# PQ60_EPS_FV2.net
KiCad netlist of a schematic drawn in EAGLE
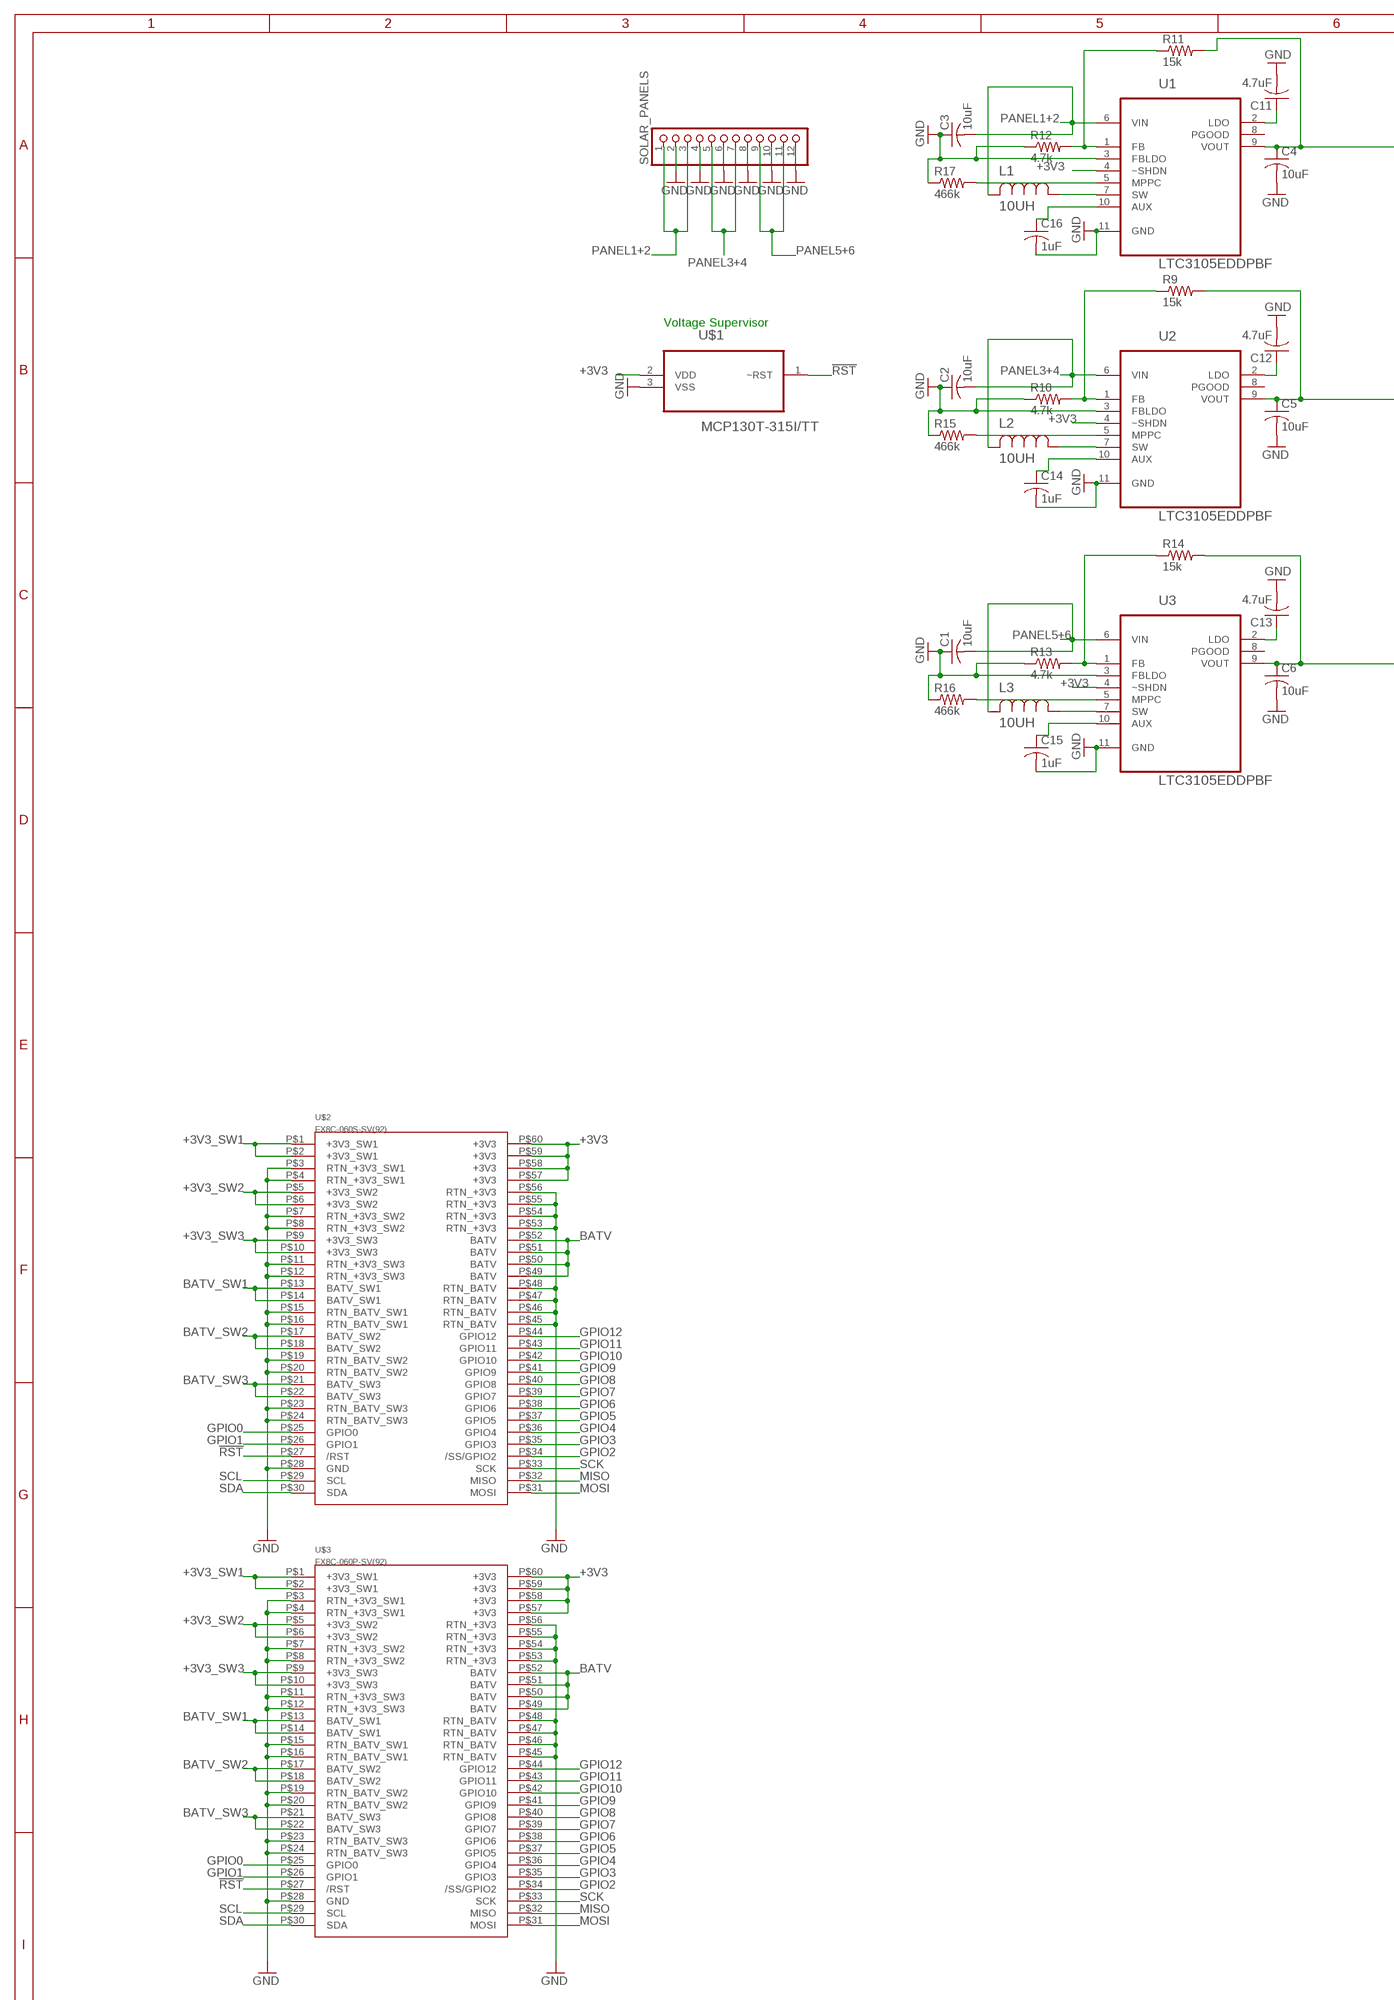
[diagram p0: schematic, sheet 1, part 1 of 2]
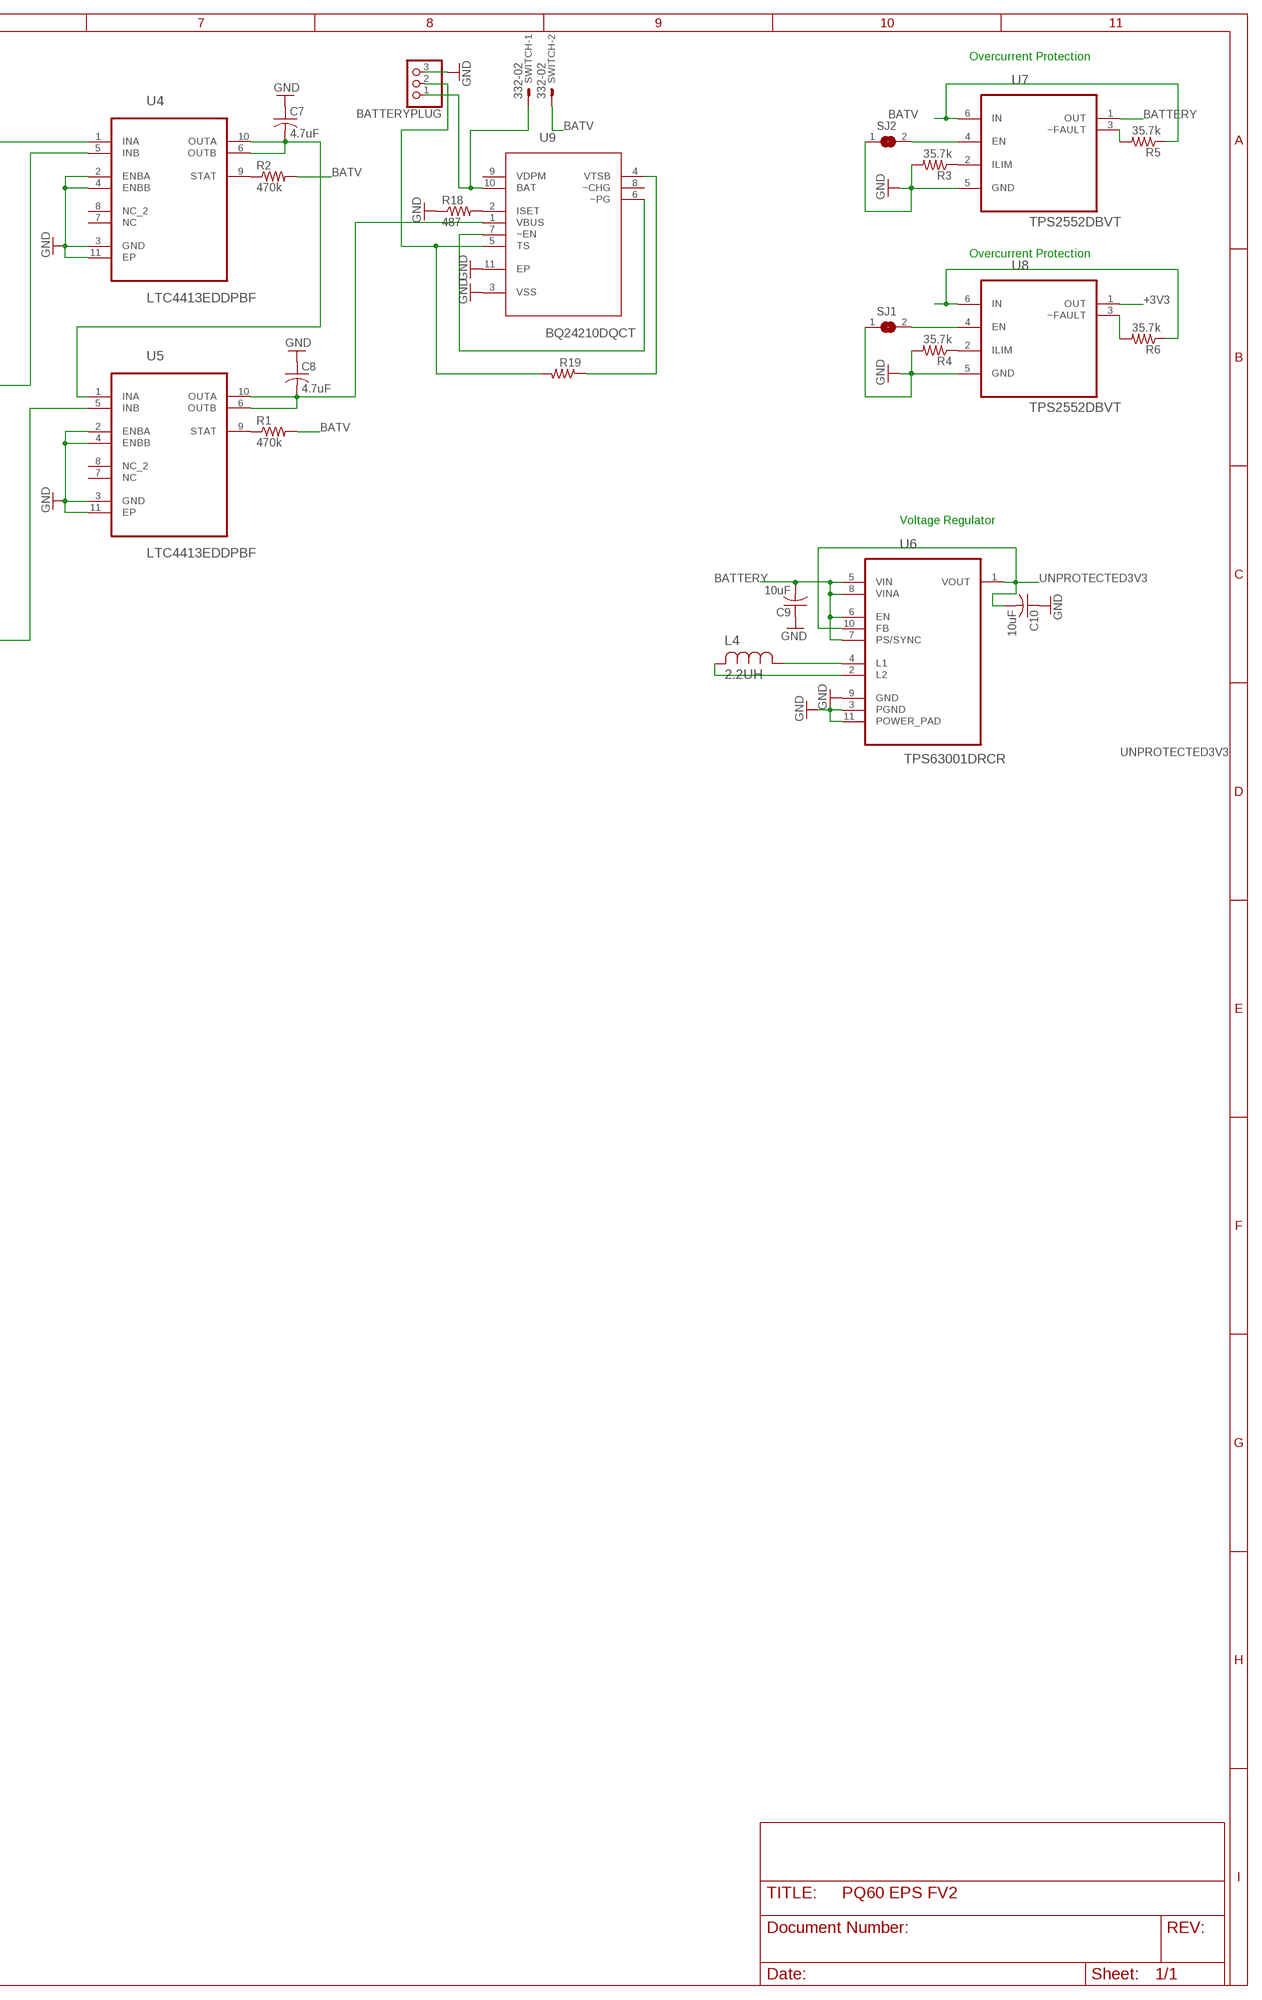
[diagram p1: schematic, sheet 1, part 2 of 2]

(export (version "E")
  (design (tool "Eeschema 10.0.6"))
  (components
    (comp (ref "BATTERYPLUG")
      (value "PINHD-1X3")
      (footprint "eagle-import:1X03")
      (libsource (lib "eagle-import") (part "PINHD-1X3"))
    )
    (comp (ref "C1")
      (value "10uF")
      (footprint "eagle-import:C0805")
      (libsource (lib "eagle-import") (part "C-USC0805"))
    )
    (comp (ref "C2")
      (value "10uF")
      (footprint "eagle-import:C0805")
      (libsource (lib "eagle-import") (part "C-USC0805"))
    )
    (comp (ref "C3")
      (value "10uF")
      (footprint "eagle-import:C0805")
      (libsource (lib "eagle-import") (part "C-USC0805"))
    )
    (comp (ref "C4")
      (value "10uF")
      (footprint "eagle-import:C0805")
      (libsource (lib "eagle-import") (part "C-USC0805"))
    )
    (comp (ref "C5")
      (value "10uF")
      (footprint "eagle-import:C0805")
      (libsource (lib "eagle-import") (part "C-USC0805"))
    )
    (comp (ref "C6")
      (value "10uF")
      (footprint "eagle-import:C0805")
      (libsource (lib "eagle-import") (part "C-USC0805"))
    )
    (comp (ref "C7")
      (value "4.7uF")
      (footprint "eagle-import:C0805")
      (libsource (lib "eagle-import") (part "C-USC0805"))
    )
    (comp (ref "C8")
      (value "4.7uF")
      (footprint "eagle-import:C0805")
      (libsource (lib "eagle-import") (part "C-USC0805"))
    )
    (comp (ref "C9")
      (value "10uF")
      (footprint "eagle-import:C0805")
      (libsource (lib "eagle-import") (part "C-USC0805"))
    )
    (comp (ref "C10")
      (value "10uF")
      (footprint "eagle-import:C0805")
      (libsource (lib "eagle-import") (part "C-USC0805"))
    )
    (comp (ref "C11")
      (value "4.7uF")
      (footprint "eagle-import:C0805")
      (libsource (lib "eagle-import") (part "C-USC0805"))
    )
    (comp (ref "C12")
      (value "4.7uF")
      (footprint "eagle-import:C0805")
      (libsource (lib "eagle-import") (part "C-USC0805"))
    )
    (comp (ref "C13")
      (value "4.7uF")
      (footprint "eagle-import:C0805")
      (libsource (lib "eagle-import") (part "C-USC0805"))
    )
    (comp (ref "C14")
      (value "1uF")
      (footprint "eagle-import:C0805")
      (libsource (lib "eagle-import") (part "C-USC0805"))
    )
    (comp (ref "C15")
      (value "1uF")
      (footprint "eagle-import:C0805")
      (libsource (lib "eagle-import") (part "C-USC0805"))
    )
    (comp (ref "C16")
      (value "1uF")
      (footprint "eagle-import:C0805")
      (libsource (lib "eagle-import") (part "C-USC0805"))
    )
    (comp (ref "L1")
      (value "10UH")
      (footprint "eagle-import:IND_ELL6XH")
      (fields (field (name "MPN") "ELL6SH100M"))
      (libsource (lib "eagle-import") (part "ELL-6XH6SH100M"))
    )
    (comp (ref "L2")
      (value "10UH")
      (footprint "eagle-import:IND_ELL6XH")
      (fields (field (name "MPN") "ELL6SH100M"))
      (libsource (lib "eagle-import") (part "ELL-6XH6SH100M"))
    )
    (comp (ref "L3")
      (value "10UH")
      (footprint "eagle-import:IND_ELL6XH")
      (fields (field (name "MPN") "ELL6SH100M"))
      (libsource (lib "eagle-import") (part "ELL-6XH6SH100M"))
    )
    (comp (ref "L4")
      (value "2.2UH")
      (footprint "eagle-import:IND_ELL3FU")
      (fields (field (name "MPN") "ELL3FU2R2N") (field (name "TOLERANCE") "±30 %"))
      (libsource (lib "eagle-import") (part "ELL-3FU3FU2R2N"))
    )
    (comp (ref "R1")
      (value "470k")
      (footprint "eagle-import:R0805")
      (libsource (lib "eagle-import") (part "R-US_R0805"))
    )
    (comp (ref "R2")
      (value "470k")
      (footprint "eagle-import:R0805")
      (libsource (lib "eagle-import") (part "R-US_R0805"))
    )
    (comp (ref "R3")
      (value "35.7k")
      (footprint "eagle-import:R0805")
      (libsource (lib "eagle-import") (part "R-US_R0805"))
    )
    (comp (ref "R4")
      (value "35.7k")
      (footprint "eagle-import:R0805")
      (libsource (lib "eagle-import") (part "R-US_R0805"))
    )
    (comp (ref "R5")
      (value "35.7k")
      (footprint "eagle-import:R0805")
      (libsource (lib "eagle-import") (part "R-US_R0805"))
    )
    (comp (ref "R6")
      (value "35.7k")
      (footprint "eagle-import:R0805")
      (libsource (lib "eagle-import") (part "R-US_R0805"))
    )
    (comp (ref "R9")
      (value "15k")
      (footprint "eagle-import:R0805")
      (libsource (lib "eagle-import") (part "R-US_R0805"))
    )
    (comp (ref "R10")
      (value "4.7k")
      (footprint "eagle-import:R0805")
      (libsource (lib "eagle-import") (part "R-US_R0805"))
    )
    (comp (ref "R11")
      (value "15k")
      (footprint "eagle-import:R0805")
      (libsource (lib "eagle-import") (part "R-US_R0805"))
    )
    (comp (ref "R12")
      (value "4.7k")
      (footprint "eagle-import:R0805")
      (libsource (lib "eagle-import") (part "R-US_R0805"))
    )
    (comp (ref "R13")
      (value "4.7k")
      (footprint "eagle-import:R0805")
      (libsource (lib "eagle-import") (part "R-US_R0805"))
    )
    (comp (ref "R14")
      (value "15k")
      (footprint "eagle-import:R0805")
      (libsource (lib "eagle-import") (part "R-US_R0805"))
    )
    (comp (ref "R15")
      (value "466k")
      (footprint "eagle-import:R0805")
      (libsource (lib "eagle-import") (part "R-US_R0805"))
    )
    (comp (ref "R16")
      (value "466k")
      (footprint "eagle-import:R0805")
      (libsource (lib "eagle-import") (part "R-US_R0805"))
    )
    (comp (ref "R17")
      (value "466k")
      (footprint "eagle-import:R0805")
      (libsource (lib "eagle-import") (part "R-US_R0805"))
    )
    (comp (ref "R18")
      (value "487")
      (footprint "eagle-import:R0805")
      (libsource (lib "eagle-import") (part "R-US_R0805"))
    )
    (comp (ref "R19")
      (value "R-US_R0805")
      (footprint "eagle-import:R0805")
      (libsource (lib "eagle-import") (part "R-US_R0805"))
    )
    (comp (ref "SJ1") (value "SJ") (footprint "eagle-import:SJ") (libsource (lib "eagle-import") (part "SJ")))
    (comp (ref "SJ2") (value "SJ") (footprint "eagle-import:SJ") (libsource (lib "eagle-import") (part "SJ")))
    (comp (ref "SOLAR_PANELS")
      (value "PINHD-1X12-CB")
      (footprint "eagle-import:1X12-CB")
      (libsource (lib "eagle-import") (part "PINHD-1X12-CB"))
    )
    (comp (ref "SWITCH")
      (value "332-02")
      (footprint "eagle-import:332-02")
      (libsource (lib "eagle-import") (part "332-02"))
    )
    (comp (ref "U$1")
      (value "MCP130T-315I/TT")
      (footprint "eagle-import:SOT95P237X112-3N")
      (libsource (lib "eagle-import") (part "MCP130T-315I/TT"))
    )
    (comp (ref "U$2")
      (value "FX8C-060S-SV(92)")
      (footprint "eagle-import:FX8C-060S-SV(92)")
      (libsource (lib "eagle-import") (part "FX8C-060S-SV(92)"))
    )
    (comp (ref "U$3")
      (value "FX8C-060P-SV(92)")
      (footprint "eagle-import:FX8C-060P-SV(92)")
      (libsource (lib "eagle-import") (part "FX8C-060P-SV(92)"))
    )
    (comp (ref "U1")
      (value "LTC3105EDDPBF")
      (footprint "eagle-import:DFN300X300X80-11N")
      (fields (field (name "MPN") "LTC3105EDD#PBF"))
      (libsource (lib "eagle-import") (part "LTC3105EDDPBF"))
    )
    (comp (ref "U2")
      (value "LTC3105EDDPBF")
      (footprint "eagle-import:DFN300X300X80-11N")
      (fields (field (name "MPN") "LTC3105EDD#PBF"))
      (libsource (lib "eagle-import") (part "LTC3105EDDPBF"))
    )
    (comp (ref "U3")
      (value "LTC3105EDDPBF")
      (footprint "eagle-import:DFN300X300X80-11N")
      (fields (field (name "MPN") "LTC3105EDD#PBF"))
      (libsource (lib "eagle-import") (part "LTC3105EDDPBF"))
    )
    (comp (ref "U4")
      (value "LTC4413EDDPBF")
      (footprint "eagle-import:DFN300X300X80-11N")
      (fields (field (name "MPN") "LTC4413EDD#PBF"))
      (libsource (lib "eagle-import") (part "LTC4413EDDPBF"))
    )
    (comp (ref "U5")
      (value "LTC4413EDDPBF")
      (footprint "eagle-import:DFN300X300X80-11N")
      (fields (field (name "MPN") "LTC4413EDD#PBF"))
      (libsource (lib "eagle-import") (part "LTC4413EDDPBF"))
    )
    (comp (ref "U6")
      (value "TPS63001DRCR")
      (footprint "eagle-import:SON50P300X300X100-11N")
      (libsource (lib "eagle-import") (part "TPS63001DRCR"))
    )
    (comp (ref "U7")
      (value "TPS2552DBVT")
      (footprint "eagle-import:SOT95P280X145-6N")
      (libsource (lib "eagle-import") (part "TPS2552DBVT"))
    )
    (comp (ref "U8")
      (value "TPS2552DBVT")
      (footprint "eagle-import:SOT95P280X145-6N")
      (libsource (lib "eagle-import") (part "TPS2552DBVT"))
    )
    (comp (ref "U9")
      (value "BQ24210DQCT")
      (footprint "eagle-import:SON50P200X300X80-11N")
      (libsource (lib "eagle-import") (part "BQ24210DQCT"))
    )
  )
  (nets
    (net (code "1") (name "/+3V3") (class "Default")
      (node (ref "U$1") (pin "2") (pinfunction "VDD_2") (pintype "power_in"))
      (node (ref "U$2") (pin "P$57") (pinfunction "+3V3_P$57") (pintype "power_in"))
      (node (ref "U$2") (pin "P$58") (pinfunction "+3V3_P$58") (pintype "power_in"))
      (node (ref "U$2") (pin "P$59") (pinfunction "+3V3_P$59") (pintype "power_in"))
      (node (ref "U$2") (pin "P$60") (pinfunction "+3V3_P$60") (pintype "power_in"))
      (node (ref "U$3") (pin "P$57") (pinfunction "+3V3_P$57") (pintype "power_in"))
      (node (ref "U$3") (pin "P$58") (pinfunction "+3V3_P$58") (pintype "power_in"))
      (node (ref "U$3") (pin "P$59") (pinfunction "+3V3_P$59") (pintype "power_in"))
      (node (ref "U$3") (pin "P$60") (pinfunction "+3V3_P$60") (pintype "power_in"))
      (node (ref "U1") (pin "4") (pinfunction "~{SHDN}_4") (pintype "input"))
      (node (ref "U2") (pin "4") (pinfunction "~{SHDN}_4") (pintype "input"))
      (node (ref "U3") (pin "4") (pinfunction "~{SHDN}_4") (pintype "input"))
      (node (ref "U8") (pin "1") (pinfunction "OUT_1") (pintype "output"))
    )
    (net (code "2") (name "/+3V3_SW1") (class "Default")
      (node (ref "U$2") (pin "P$1") (pinfunction "+3V3_SW1_P$1") (pintype "power_in"))
      (node (ref "U$2") (pin "P$2") (pinfunction "+3V3_SW1_P$2") (pintype "power_in"))
      (node (ref "U$3") (pin "P$1") (pinfunction "+3V3_SW1_P$1") (pintype "power_in"))
      (node (ref "U$3") (pin "P$2") (pinfunction "+3V3_SW1_P$2") (pintype "power_in"))
    )
    (net (code "3") (name "/+3V3_SW2") (class "Default")
      (node (ref "U$2") (pin "P$5") (pinfunction "+3V3_SW2_P$5") (pintype "power_in"))
      (node (ref "U$2") (pin "P$6") (pinfunction "+3V3_SW2_P$6") (pintype "power_in"))
      (node (ref "U$3") (pin "P$5") (pinfunction "+3V3_SW2_P$5") (pintype "power_in"))
      (node (ref "U$3") (pin "P$6") (pinfunction "+3V3_SW2_P$6") (pintype "power_in"))
    )
    (net (code "4") (name "/+3V3_SW3") (class "Default")
      (node (ref "U$2") (pin "P$10") (pinfunction "+3V3_SW3_P$10") (pintype "power_in"))
      (node (ref "U$2") (pin "P$9") (pinfunction "+3V3_SW3_P$9") (pintype "power_in"))
      (node (ref "U$3") (pin "P$10") (pinfunction "+3V3_SW3_P$10") (pintype "power_in"))
      (node (ref "U$3") (pin "P$9") (pinfunction "+3V3_SW3_P$9") (pintype "power_in"))
    )
    (net (code "5") (name "/BATTERY") (class "Default")
      (node (ref "C9") (pin "2") (pinfunction "2_2") (pintype "passive"))
      (node (ref "U6") (pin "5") (pinfunction "VIN_5") (pintype "power_in"))
      (node (ref "U6") (pin "6") (pinfunction "EN_6") (pintype "input"))
      (node (ref "U6") (pin "7") (pinfunction "PS/SYNC_7") (pintype "input"))
      (node (ref "U6") (pin "8") (pinfunction "VINA_8") (pintype "power_in"))
      (node (ref "U7") (pin "1") (pinfunction "OUT_1") (pintype "output"))
    )
    (net (code "6") (name "/BATV") (class "Default")
      (node (ref "R1") (pin "2") (pinfunction "2_2") (pintype "passive"))
      (node (ref "R2") (pin "2") (pinfunction "2_2") (pintype "passive"))
      (node (ref "R5") (pin "1") (pinfunction "1_1") (pintype "passive"))
      (node (ref "SWITCH") (pin "2") (pinfunction "S_2") (pintype "passive"))
      (node (ref "U$2") (pin "P$49") (pinfunction "BATV_P$49") (pintype "power_in"))
      (node (ref "U$2") (pin "P$50") (pinfunction "BATV_P$50") (pintype "power_in"))
      (node (ref "U$2") (pin "P$51") (pinfunction "BATV_P$51") (pintype "power_in"))
      (node (ref "U$2") (pin "P$52") (pinfunction "BATV_P$52") (pintype "power_in"))
      (node (ref "U$3") (pin "P$49") (pinfunction "BATV_P$49") (pintype "power_in"))
      (node (ref "U$3") (pin "P$50") (pinfunction "BATV_P$50") (pintype "power_in"))
      (node (ref "U$3") (pin "P$51") (pinfunction "BATV_P$51") (pintype "power_in"))
      (node (ref "U$3") (pin "P$52") (pinfunction "BATV_P$52") (pintype "power_in"))
      (node (ref "U7") (pin "6") (pinfunction "IN_6") (pintype "power_in"))
    )
    (net (code "7") (name "/BATV_SW1") (class "Default")
      (node (ref "U$2") (pin "P$13") (pinfunction "BATV_SW1_P$13") (pintype "power_in"))
      (node (ref "U$2") (pin "P$14") (pinfunction "BATV_SW1_P$14") (pintype "power_in"))
      (node (ref "U$3") (pin "P$13") (pinfunction "BATV_SW1_P$13") (pintype "power_in"))
      (node (ref "U$3") (pin "P$14") (pinfunction "BATV_SW1_P$14") (pintype "power_in"))
    )
    (net (code "8") (name "/BATV_SW2") (class "Default")
      (node (ref "U$2") (pin "P$17") (pinfunction "BATV_SW2_P$17") (pintype "power_in"))
      (node (ref "U$2") (pin "P$18") (pinfunction "BATV_SW2_P$18") (pintype "power_in"))
      (node (ref "U$3") (pin "P$17") (pinfunction "BATV_SW2_P$17") (pintype "power_in"))
      (node (ref "U$3") (pin "P$18") (pinfunction "BATV_SW2_P$18") (pintype "power_in"))
    )
    (net (code "9") (name "/BATV_SW3") (class "Default")
      (node (ref "U$2") (pin "P$21") (pinfunction "BATV_SW3_P$21") (pintype "power_in"))
      (node (ref "U$2") (pin "P$22") (pinfunction "BATV_SW3_P$22") (pintype "power_in"))
      (node (ref "U$3") (pin "P$21") (pinfunction "BATV_SW3_P$21") (pintype "power_in"))
      (node (ref "U$3") (pin "P$22") (pinfunction "BATV_SW3_P$22") (pintype "power_in"))
    )
    (net (code "10") (name "/GPIO0") (class "Default")
      (node (ref "U$2") (pin "P$25") (pinfunction "GPIO0_P$25") (pintype "bidirectional"))
      (node (ref "U$3") (pin "P$25") (pinfunction "GPIO0_P$25") (pintype "bidirectional"))
    )
    (net (code "11") (name "/GPIO1") (class "Default")
      (node (ref "U$2") (pin "P$26") (pinfunction "GPIO1_P$26") (pintype "bidirectional"))
      (node (ref "U$3") (pin "P$26") (pinfunction "GPIO1_P$26") (pintype "bidirectional"))
    )
    (net (code "12") (name "/GPIO2") (class "Default")
      (node (ref "U$2") (pin "P$34") (pinfunction "/SS/GPIO2_P$34") (pintype "bidirectional"))
      (node (ref "U$3") (pin "P$34") (pinfunction "/SS/GPIO2_P$34") (pintype "bidirectional"))
    )
    (net (code "13") (name "/GPIO3") (class "Default")
      (node (ref "U$2") (pin "P$35") (pinfunction "GPIO3_P$35") (pintype "bidirectional"))
      (node (ref "U$3") (pin "P$35") (pinfunction "GPIO3_P$35") (pintype "bidirectional"))
    )
    (net (code "14") (name "/GPIO4") (class "Default")
      (node (ref "U$2") (pin "P$36") (pinfunction "GPIO4_P$36") (pintype "bidirectional"))
      (node (ref "U$3") (pin "P$36") (pinfunction "GPIO4_P$36") (pintype "bidirectional"))
    )
    (net (code "15") (name "/GPIO5") (class "Default")
      (node (ref "U$2") (pin "P$37") (pinfunction "GPIO5_P$37") (pintype "bidirectional"))
      (node (ref "U$3") (pin "P$37") (pinfunction "GPIO5_P$37") (pintype "bidirectional"))
    )
    (net (code "16") (name "/GPIO6") (class "Default")
      (node (ref "U$2") (pin "P$38") (pinfunction "GPIO6_P$38") (pintype "bidirectional"))
      (node (ref "U$3") (pin "P$38") (pinfunction "GPIO6_P$38") (pintype "bidirectional"))
    )
    (net (code "17") (name "/GPIO7") (class "Default")
      (node (ref "U$2") (pin "P$39") (pinfunction "GPIO7_P$39") (pintype "bidirectional"))
      (node (ref "U$3") (pin "P$39") (pinfunction "GPIO7_P$39") (pintype "bidirectional"))
    )
    (net (code "18") (name "/GPIO8") (class "Default")
      (node (ref "U$2") (pin "P$40") (pinfunction "GPIO8_P$40") (pintype "bidirectional"))
      (node (ref "U$3") (pin "P$40") (pinfunction "GPIO8_P$40") (pintype "bidirectional"))
    )
    (net (code "19") (name "/GPIO9") (class "Default")
      (node (ref "U$2") (pin "P$41") (pinfunction "GPIO9_P$41") (pintype "bidirectional"))
      (node (ref "U$3") (pin "P$41") (pinfunction "GPIO9_P$41") (pintype "bidirectional"))
    )
    (net (code "20") (name "/GPIO10") (class "Default")
      (node (ref "U$2") (pin "P$42") (pinfunction "GPIO10_P$42") (pintype "bidirectional"))
      (node (ref "U$3") (pin "P$42") (pinfunction "GPIO10_P$42") (pintype "bidirectional"))
    )
    (net (code "21") (name "/GPIO11") (class "Default")
      (node (ref "U$2") (pin "P$43") (pinfunction "GPIO11_P$43") (pintype "bidirectional"))
      (node (ref "U$3") (pin "P$43") (pinfunction "GPIO11_P$43") (pintype "bidirectional"))
    )
    (net (code "22") (name "/GPIO12") (class "Default")
      (node (ref "U$2") (pin "P$44") (pinfunction "GPIO12_P$44") (pintype "bidirectional"))
      (node (ref "U$3") (pin "P$44") (pinfunction "GPIO12_P$44") (pintype "bidirectional"))
    )
    (net (code "23") (name "/MISO") (class "Default")
      (node (ref "U$2") (pin "P$32") (pinfunction "MISO_P$32") (pintype "bidirectional"))
      (node (ref "U$3") (pin "P$32") (pinfunction "MISO_P$32") (pintype "bidirectional"))
    )
    (net (code "24") (name "/MOSI") (class "Default")
      (node (ref "U$2") (pin "P$31") (pinfunction "MOSI_P$31") (pintype "bidirectional"))
      (node (ref "U$3") (pin "P$31") (pinfunction "MOSI_P$31") (pintype "bidirectional"))
    )
    (net (code "25") (name "/PANEL1+2") (class "Default")
      (node (ref "C3") (pin "2") (pinfunction "2_2") (pintype "passive"))
      (node (ref "L1") (pin "2") (pinfunction "2_2") (pintype "passive"))
      (node (ref "SOLAR_PANELS") (pin "1") (pinfunction "1_1") (pintype "passive"))
      (node (ref "SOLAR_PANELS") (pin "3") (pinfunction "3_3") (pintype "passive"))
      (node (ref "U1") (pin "6") (pinfunction "VIN_6") (pintype "power_in"))
    )
    (net (code "26") (name "/PANEL3+4") (class "Default")
      (node (ref "C2") (pin "2") (pinfunction "2_2") (pintype "passive"))
      (node (ref "L2") (pin "2") (pinfunction "2_2") (pintype "passive"))
      (node (ref "SOLAR_PANELS") (pin "5") (pinfunction "5_5") (pintype "passive"))
      (node (ref "SOLAR_PANELS") (pin "7") (pinfunction "7_7") (pintype "passive"))
      (node (ref "U2") (pin "6") (pinfunction "VIN_6") (pintype "power_in"))
    )
    (net (code "27") (name "/PANEL5+6") (class "Default")
      (node (ref "C1") (pin "2") (pinfunction "2_2") (pintype "passive"))
      (node (ref "L3") (pin "2") (pinfunction "2_2") (pintype "passive"))
      (node (ref "SOLAR_PANELS") (pin "11") (pinfunction "11_11") (pintype "passive"))
      (node (ref "SOLAR_PANELS") (pin "9") (pinfunction "9_9") (pintype "passive"))
      (node (ref "U3") (pin "6") (pinfunction "VIN_6") (pintype "power_in"))
    )
    (net (code "28") (name "/SCK") (class "Default")
      (node (ref "U$2") (pin "P$33") (pinfunction "SCK_P$33") (pintype "bidirectional"))
      (node (ref "U$3") (pin "P$33") (pinfunction "SCK_P$33") (pintype "bidirectional"))
    )
    (net (code "29") (name "/SCL") (class "Default")
      (node (ref "U$2") (pin "P$29") (pinfunction "SCL_P$29") (pintype "bidirectional"))
      (node (ref "U$3") (pin "P$29") (pinfunction "SCL_P$29") (pintype "bidirectional"))
    )
    (net (code "30") (name "/SDA") (class "Default")
      (node (ref "U$2") (pin "P$30") (pinfunction "SDA_P$30") (pintype "bidirectional"))
      (node (ref "U$3") (pin "P$30") (pinfunction "SDA_P$30") (pintype "bidirectional"))
    )
    (net (code "31") (name "/UNPROTECTED3V3") (class "Default")
      (node (ref "C10") (pin "2") (pinfunction "2_2") (pintype "passive"))
      (node (ref "R6") (pin "1") (pinfunction "1_1") (pintype "passive"))
      (node (ref "U6") (pin "1") (pinfunction "VOUT_1") (pintype "output"))
      (node (ref "U6") (pin "10") (pinfunction "FB_10") (pintype "input"))
      (node (ref "U8") (pin "6") (pinfunction "IN_6") (pintype "power_in"))
    )
    (net (code "32") (name "/~{RST}") (class "Default")
      (node (ref "U$1") (pin "1") (pinfunction "~{RST}_1") (pintype "output"))
      (node (ref "U$2") (pin "P$27") (pinfunction "/RST_P$27") (pintype "bidirectional"))
      (node (ref "U$3") (pin "P$27") (pinfunction "/RST_P$27") (pintype "bidirectional"))
    )
    (net (code "33") (name "GND") (class "Default")
      (node (ref "BATTERYPLUG") (pin "3") (pinfunction "3_3") (pintype "passive"))
      (node (ref "C1") (pin "1") (pinfunction "1_1") (pintype "passive"))
      (node (ref "C10") (pin "1") (pinfunction "1_1") (pintype "passive"))
      (node (ref "C11") (pin "2") (pinfunction "2_2") (pintype "passive"))
      (node (ref "C12") (pin "2") (pinfunction "2_2") (pintype "passive"))
      (node (ref "C13") (pin "2") (pinfunction "2_2") (pintype "passive"))
      (node (ref "C14") (pin "2") (pinfunction "2_2") (pintype "passive"))
      (node (ref "C15") (pin "2") (pinfunction "2_2") (pintype "passive"))
      (node (ref "C16") (pin "2") (pinfunction "2_2") (pintype "passive"))
      (node (ref "C2") (pin "1") (pinfunction "1_1") (pintype "passive"))
      (node (ref "C3") (pin "1") (pinfunction "1_1") (pintype "passive"))
      (node (ref "C4") (pin "2") (pinfunction "2_2") (pintype "passive"))
      (node (ref "C5") (pin "2") (pinfunction "2_2") (pintype "passive"))
      (node (ref "C6") (pin "2") (pinfunction "2_2") (pintype "passive"))
      (node (ref "C7") (pin "1") (pinfunction "1_1") (pintype "passive"))
      (node (ref "C8") (pin "1") (pinfunction "1_1") (pintype "passive"))
      (node (ref "C9") (pin "1") (pinfunction "1_1") (pintype "passive"))
      (node (ref "R10") (pin "1") (pinfunction "1_1") (pintype "passive"))
      (node (ref "R12") (pin "1") (pinfunction "1_1") (pintype "passive"))
      (node (ref "R13") (pin "1") (pinfunction "1_1") (pintype "passive"))
      (node (ref "R15") (pin "1") (pinfunction "1_1") (pintype "passive"))
      (node (ref "R16") (pin "1") (pinfunction "1_1") (pintype "passive"))
      (node (ref "R17") (pin "1") (pinfunction "1_1") (pintype "passive"))
      (node (ref "R18") (pin "1") (pinfunction "1_1") (pintype "passive"))
      (node (ref "R3") (pin "2") (pinfunction "2_2") (pintype "passive"))
      (node (ref "R4") (pin "2") (pinfunction "2_2") (pintype "passive"))
      (node (ref "SJ1") (pin "1") (pinfunction "1_1") (pintype "passive"))
      (node (ref "SJ2") (pin "1") (pinfunction "1_1") (pintype "passive"))
      (node (ref "SOLAR_PANELS") (pin "10") (pinfunction "10_10") (pintype "passive"))
      (node (ref "SOLAR_PANELS") (pin "12") (pinfunction "12_12") (pintype "passive"))
      (node (ref "SOLAR_PANELS") (pin "2") (pinfunction "2_2") (pintype "passive"))
      (node (ref "SOLAR_PANELS") (pin "4") (pinfunction "4_4") (pintype "passive"))
      (node (ref "SOLAR_PANELS") (pin "6") (pinfunction "6_6") (pintype "passive"))
      (node (ref "SOLAR_PANELS") (pin "8") (pinfunction "8_8") (pintype "passive"))
      (node (ref "U$1") (pin "3") (pinfunction "VSS_3") (pintype "power_in"))
      (node (ref "U$2") (pin "P$11") (pinfunction "RTN_+3V3_SW3_P$11") (pintype "power_in"))
      (node (ref "U$2") (pin "P$12") (pinfunction "RTN_+3V3_SW3_P$12") (pintype "power_in"))
      (node (ref "U$2") (pin "P$15") (pinfunction "RTN_BATV_SW1_P$15") (pintype "power_in"))
      (node (ref "U$2") (pin "P$16") (pinfunction "RTN_BATV_SW1_P$16") (pintype "power_in"))
      (node (ref "U$2") (pin "P$19") (pinfunction "RTN_BATV_SW2_P$19") (pintype "power_in"))
      (node (ref "U$2") (pin "P$20") (pinfunction "RTN_BATV_SW2_P$20") (pintype "power_in"))
      (node (ref "U$2") (pin "P$23") (pinfunction "RTN_BATV_SW3_P$23") (pintype "power_in"))
      (node (ref "U$2") (pin "P$24") (pinfunction "RTN_BATV_SW3_P$24") (pintype "power_in"))
      (node (ref "U$2") (pin "P$28") (pinfunction "GND_P$28") (pintype "bidirectional"))
      (node (ref "U$2") (pin "P$3") (pinfunction "RTN_+3V3_SW1_P$3") (pintype "power_in"))
      (node (ref "U$2") (pin "P$4") (pinfunction "RTN_+3V3_SW1_P$4") (pintype "power_in"))
      (node (ref "U$2") (pin "P$45") (pinfunction "RTN_BATV_P$45") (pintype "power_in"))
      (node (ref "U$2") (pin "P$46") (pinfunction "RTN_BATV_P$46") (pintype "power_in"))
      (node (ref "U$2") (pin "P$47") (pinfunction "RTN_BATV_P$47") (pintype "power_in"))
      (node (ref "U$2") (pin "P$48") (pinfunction "RTN_BATV_P$48") (pintype "power_in"))
      (node (ref "U$2") (pin "P$53") (pinfunction "RTN_+3V3_P$53") (pintype "power_in"))
      (node (ref "U$2") (pin "P$54") (pinfunction "RTN_+3V3_P$54") (pintype "power_in"))
      (node (ref "U$2") (pin "P$55") (pinfunction "RTN_+3V3_P$55") (pintype "power_in"))
      (node (ref "U$2") (pin "P$56") (pinfunction "RTN_+3V3_P$56") (pintype "power_in"))
      (node (ref "U$2") (pin "P$7") (pinfunction "RTN_+3V3_SW2_P$7") (pintype "power_in"))
      (node (ref "U$2") (pin "P$8") (pinfunction "RTN_+3V3_SW2_P$8") (pintype "power_in"))
      (node (ref "U$3") (pin "P$11") (pinfunction "RTN_+3V3_SW3_P$11") (pintype "power_in"))
      (node (ref "U$3") (pin "P$12") (pinfunction "RTN_+3V3_SW3_P$12") (pintype "power_in"))
      (node (ref "U$3") (pin "P$15") (pinfunction "RTN_BATV_SW1_P$15") (pintype "power_in"))
      (node (ref "U$3") (pin "P$16") (pinfunction "RTN_BATV_SW1_P$16") (pintype "power_in"))
      (node (ref "U$3") (pin "P$19") (pinfunction "RTN_BATV_SW2_P$19") (pintype "power_in"))
      (node (ref "U$3") (pin "P$20") (pinfunction "RTN_BATV_SW2_P$20") (pintype "power_in"))
      (node (ref "U$3") (pin "P$23") (pinfunction "RTN_BATV_SW3_P$23") (pintype "power_in"))
      (node (ref "U$3") (pin "P$24") (pinfunction "RTN_BATV_SW3_P$24") (pintype "power_in"))
      (node (ref "U$3") (pin "P$28") (pinfunction "GND_P$28") (pintype "bidirectional"))
      (node (ref "U$3") (pin "P$3") (pinfunction "RTN_+3V3_SW1_P$3") (pintype "power_in"))
      (node (ref "U$3") (pin "P$4") (pinfunction "RTN_+3V3_SW1_P$4") (pintype "power_in"))
      (node (ref "U$3") (pin "P$45") (pinfunction "RTN_BATV_P$45") (pintype "power_in"))
      (node (ref "U$3") (pin "P$46") (pinfunction "RTN_BATV_P$46") (pintype "power_in"))
      (node (ref "U$3") (pin "P$47") (pinfunction "RTN_BATV_P$47") (pintype "power_in"))
      (node (ref "U$3") (pin "P$48") (pinfunction "RTN_BATV_P$48") (pintype "power_in"))
      (node (ref "U$3") (pin "P$53") (pinfunction "RTN_+3V3_P$53") (pintype "power_in"))
      (node (ref "U$3") (pin "P$54") (pinfunction "RTN_+3V3_P$54") (pintype "power_in"))
      (node (ref "U$3") (pin "P$55") (pinfunction "RTN_+3V3_P$55") (pintype "power_in"))
      (node (ref "U$3") (pin "P$56") (pinfunction "RTN_+3V3_P$56") (pintype "power_in"))
      (node (ref "U$3") (pin "P$7") (pinfunction "RTN_+3V3_SW2_P$7") (pintype "power_in"))
      (node (ref "U$3") (pin "P$8") (pinfunction "RTN_+3V3_SW2_P$8") (pintype "power_in"))
      (node (ref "U1") (pin "11") (pinfunction "GND_11") (pintype "passive"))
      (node (ref "U1") (pin "3") (pinfunction "FBLDO_3") (pintype "input"))
      (node (ref "U2") (pin "11") (pinfunction "GND_11") (pintype "passive"))
      (node (ref "U2") (pin "3") (pinfunction "FBLDO_3") (pintype "input"))
      (node (ref "U3") (pin "11") (pinfunction "GND_11") (pintype "passive"))
      (node (ref "U3") (pin "3") (pinfunction "FBLDO_3") (pintype "input"))
      (node (ref "U4") (pin "11") (pinfunction "EP_11") (pintype "passive"))
      (node (ref "U4") (pin "2") (pinfunction "ENBA_2") (pintype "input"))
      (node (ref "U4") (pin "3") (pinfunction "GND_3") (pintype "passive"))
      (node (ref "U4") (pin "4") (pinfunction "ENBB_4") (pintype "input"))
      (node (ref "U5") (pin "11") (pinfunction "EP_11") (pintype "passive"))
      (node (ref "U5") (pin "2") (pinfunction "ENBA_2") (pintype "input"))
      (node (ref "U5") (pin "3") (pinfunction "GND_3") (pintype "passive"))
      (node (ref "U5") (pin "4") (pinfunction "ENBB_4") (pintype "input"))
      (node (ref "U6") (pin "11") (pinfunction "POWER_PAD_11") (pintype "passive"))
      (node (ref "U6") (pin "3") (pinfunction "PGND_3") (pintype "passive"))
      (node (ref "U6") (pin "9") (pinfunction "GND_9") (pintype "passive"))
      (node (ref "U7") (pin "5") (pinfunction "GND_5") (pintype "passive"))
      (node (ref "U8") (pin "5") (pinfunction "GND_5") (pintype "passive"))
      (node (ref "U9") (pin "11") (pinfunction "EP_11") (pintype "passive"))
      (node (ref "U9") (pin "3") (pinfunction "VSS_3") (pintype "passive"))
    )
    (net (code "34") (name "Net-(SWITCHA-S)") (class "Default")
      (node (ref "BATTERYPLUG") (pin "1") (pinfunction "1_1") (pintype "passive"))
      (node (ref "SWITCH") (pin "1") (pinfunction "S_1") (pintype "passive"))
      (node (ref "U9") (pin "10") (pinfunction "BAT_10") (pintype "bidirectional"))
    )
    (net (code "35") (name "Net-(U1-AUX)") (class "Default")
      (node (ref "C16") (pin "1") (pinfunction "1_1") (pintype "passive"))
      (node (ref "U1") (pin "10") (pinfunction "AUX_10") (pintype "passive"))
    )
    (net (code "36") (name "Net-(U1-FB)") (class "Default")
      (node (ref "R11") (pin "1") (pinfunction "1_1") (pintype "passive"))
      (node (ref "R12") (pin "2") (pinfunction "2_2") (pintype "passive"))
      (node (ref "U1") (pin "1") (pinfunction "FB_1") (pintype "input"))
    )
    (net (code "37") (name "Net-(U1-LDO)") (class "Default")
      (node (ref "C11") (pin "1") (pinfunction "1_1") (pintype "passive"))
      (node (ref "U1") (pin "2") (pinfunction "LDO_2") (pintype "output"))
    )
    (net (code "38") (name "Net-(U1-MPPC)") (class "Default")
      (node (ref "R17") (pin "2") (pinfunction "2_2") (pintype "passive"))
      (node (ref "U1") (pin "5") (pinfunction "MPPC_5") (pintype "input"))
    )
    (net (code "39") (name "Net-(U1-SW)") (class "Default")
      (node (ref "L1") (pin "1") (pinfunction "1_1") (pintype "passive"))
      (node (ref "U1") (pin "7") (pinfunction "SW_7") (pintype "passive"))
    )
    (net (code "40") (name "Net-(U1-VOUT)") (class "Default")
      (node (ref "C4") (pin "1") (pinfunction "1_1") (pintype "passive"))
      (node (ref "R11") (pin "2") (pinfunction "2_2") (pintype "passive"))
      (node (ref "U1") (pin "9") (pinfunction "VOUT_9") (pintype "output"))
      (node (ref "U4") (pin "1") (pinfunction "INA_1") (pintype "power_in"))
    )
    (net (code "41") (name "Net-(U2-AUX)") (class "Default")
      (node (ref "C14") (pin "1") (pinfunction "1_1") (pintype "passive"))
      (node (ref "U2") (pin "10") (pinfunction "AUX_10") (pintype "passive"))
    )
    (net (code "42") (name "Net-(U2-FB)") (class "Default")
      (node (ref "R10") (pin "2") (pinfunction "2_2") (pintype "passive"))
      (node (ref "R9") (pin "1") (pinfunction "1_1") (pintype "passive"))
      (node (ref "U2") (pin "1") (pinfunction "FB_1") (pintype "input"))
    )
    (net (code "43") (name "Net-(U2-LDO)") (class "Default")
      (node (ref "C12") (pin "1") (pinfunction "1_1") (pintype "passive"))
      (node (ref "U2") (pin "2") (pinfunction "LDO_2") (pintype "output"))
    )
    (net (code "44") (name "Net-(U2-MPPC)") (class "Default")
      (node (ref "R15") (pin "2") (pinfunction "2_2") (pintype "passive"))
      (node (ref "U2") (pin "5") (pinfunction "MPPC_5") (pintype "input"))
    )
    (net (code "45") (name "Net-(U2-SW)") (class "Default")
      (node (ref "L2") (pin "1") (pinfunction "1_1") (pintype "passive"))
      (node (ref "U2") (pin "7") (pinfunction "SW_7") (pintype "passive"))
    )
    (net (code "46") (name "Net-(U2-VOUT)") (class "Default")
      (node (ref "C5") (pin "1") (pinfunction "1_1") (pintype "passive"))
      (node (ref "R9") (pin "2") (pinfunction "2_2") (pintype "passive"))
      (node (ref "U2") (pin "9") (pinfunction "VOUT_9") (pintype "output"))
      (node (ref "U4") (pin "5") (pinfunction "INB_5") (pintype "power_in"))
    )
    (net (code "47") (name "Net-(U3-AUX)") (class "Default")
      (node (ref "C15") (pin "1") (pinfunction "1_1") (pintype "passive"))
      (node (ref "U3") (pin "10") (pinfunction "AUX_10") (pintype "passive"))
    )
    (net (code "48") (name "Net-(U3-FB)") (class "Default")
      (node (ref "R13") (pin "2") (pinfunction "2_2") (pintype "passive"))
      (node (ref "R14") (pin "1") (pinfunction "1_1") (pintype "passive"))
      (node (ref "U3") (pin "1") (pinfunction "FB_1") (pintype "input"))
    )
    (net (code "49") (name "Net-(U3-LDO)") (class "Default")
      (node (ref "C13") (pin "1") (pinfunction "1_1") (pintype "passive"))
      (node (ref "U3") (pin "2") (pinfunction "LDO_2") (pintype "output"))
    )
    (net (code "50") (name "Net-(U3-MPPC)") (class "Default")
      (node (ref "R16") (pin "2") (pinfunction "2_2") (pintype "passive"))
      (node (ref "U3") (pin "5") (pinfunction "MPPC_5") (pintype "input"))
    )
    (net (code "51") (name "Net-(U3-SW)") (class "Default")
      (node (ref "L3") (pin "1") (pinfunction "1_1") (pintype "passive"))
      (node (ref "U3") (pin "7") (pinfunction "SW_7") (pintype "passive"))
    )
    (net (code "52") (name "Net-(U3-VOUT)") (class "Default")
      (node (ref "C6") (pin "1") (pinfunction "1_1") (pintype "passive"))
      (node (ref "R14") (pin "2") (pinfunction "2_2") (pintype "passive"))
      (node (ref "U3") (pin "9") (pinfunction "VOUT_9") (pintype "output"))
      (node (ref "U5") (pin "5") (pinfunction "INB_5") (pintype "power_in"))
    )
    (net (code "53") (name "Net-(U4-OUTA)") (class "Default")
      (node (ref "C7") (pin "2") (pinfunction "2_2") (pintype "passive"))
      (node (ref "U4") (pin "10") (pinfunction "OUTA_10") (pintype "output"))
      (node (ref "U4") (pin "6") (pinfunction "OUTB_6") (pintype "output"))
      (node (ref "U5") (pin "1") (pinfunction "INA_1") (pintype "power_in"))
    )
    (net (code "54") (name "Net-(U4-STAT)") (class "Default")
      (node (ref "R2") (pin "1") (pinfunction "1_1") (pintype "passive"))
      (node (ref "U4") (pin "9") (pinfunction "STAT_9") (pintype "output"))
    )
    (net (code "55") (name "Net-(U5-OUTA)") (class "Default")
      (node (ref "C8") (pin "2") (pinfunction "2_2") (pintype "passive"))
      (node (ref "U5") (pin "10") (pinfunction "OUTA_10") (pintype "output"))
      (node (ref "U5") (pin "6") (pinfunction "OUTB_6") (pintype "output"))
      (node (ref "U9") (pin "1") (pinfunction "VBUS_1") (pintype "bidirectional"))
    )
    (net (code "56") (name "Net-(U5-STAT)") (class "Default")
      (node (ref "R1") (pin "1") (pinfunction "1_1") (pintype "passive"))
      (node (ref "U5") (pin "9") (pinfunction "STAT_9") (pintype "output"))
    )
    (net (code "57") (name "Net-(U6-L1)") (class "Default")
      (node (ref "L4") (pin "1") (pinfunction "1_1") (pintype "passive"))
      (node (ref "U6") (pin "4") (pinfunction "L1_4") (pintype "passive"))
    )
    (net (code "58") (name "Net-(U6-L2)") (class "Default")
      (node (ref "L4") (pin "2") (pinfunction "2_2") (pintype "passive"))
      (node (ref "U6") (pin "2") (pinfunction "L2_2") (pintype "passive"))
    )
    (net (code "59") (name "Net-(U7-EN)") (class "Default")
      (node (ref "SJ2") (pin "2") (pinfunction "2_2") (pintype "passive"))
      (node (ref "U7") (pin "4") (pinfunction "EN_4") (pintype "input"))
    )
    (net (code "60") (name "Net-(U7-ILIM)") (class "Default")
      (node (ref "R3") (pin "1") (pinfunction "1_1") (pintype "passive"))
      (node (ref "U7") (pin "2") (pinfunction "ILIM_2") (pintype "input"))
    )
    (net (code "61") (name "Net-(U7-~{FAULT})") (class "Default")
      (node (ref "R5") (pin "2") (pinfunction "2_2") (pintype "passive"))
      (node (ref "U7") (pin "3") (pinfunction "~{FAULT}_3") (pintype "output"))
    )
    (net (code "62") (name "Net-(U8-EN)") (class "Default")
      (node (ref "SJ1") (pin "2") (pinfunction "2_2") (pintype "passive"))
      (node (ref "U8") (pin "4") (pinfunction "EN_4") (pintype "input"))
    )
    (net (code "63") (name "Net-(U8-ILIM)") (class "Default")
      (node (ref "R4") (pin "1") (pinfunction "1_1") (pintype "passive"))
      (node (ref "U8") (pin "2") (pinfunction "ILIM_2") (pintype "input"))
    )
    (net (code "64") (name "Net-(U8-~{FAULT})") (class "Default")
      (node (ref "R6") (pin "2") (pinfunction "2_2") (pintype "passive"))
      (node (ref "U8") (pin "3") (pinfunction "~{FAULT}_3") (pintype "output"))
    )
    (net (code "65") (name "Net-(U9-ISET)") (class "Default")
      (node (ref "R18") (pin "2") (pinfunction "2_2") (pintype "passive"))
      (node (ref "U9") (pin "2") (pinfunction "ISET_2") (pintype "input"))
    )
    (net (code "66") (name "Net-(U9-TS)") (class "Default")
      (node (ref "BATTERYPLUG") (pin "2") (pinfunction "2_2") (pintype "passive"))
      (node (ref "R19") (pin "2") (pinfunction "2_2") (pintype "passive"))
      (node (ref "U9") (pin "5") (pinfunction "TS_5") (pintype "input"))
    )
    (net (code "67") (name "Net-(U9-VTSB)") (class "Default")
      (node (ref "R19") (pin "1") (pinfunction "1_1") (pintype "passive"))
      (node (ref "U9") (pin "4") (pinfunction "VTSB_4") (pintype "output"))
    )
    (net (code "68") (name "Net-(U9-~{EN})") (class "Default")
      (node (ref "U9") (pin "6") (pinfunction "~{PG}_6") (pintype "output"))
      (node (ref "U9") (pin "7") (pinfunction "~{EN}_7") (pintype "input"))
    )
    (net (code "69") (name "unconnected-(U1-PGOOD-Pad8)") (class "Default")
      (node (ref "U1") (pin "8") (pinfunction "PGOOD_8") (pintype "output"))
    )
    (net (code "70") (name "unconnected-(U2-PGOOD-Pad8)") (class "Default")
      (node (ref "U2") (pin "8") (pinfunction "PGOOD_8") (pintype "output"))
    )
    (net (code "71") (name "unconnected-(U3-PGOOD-Pad8)") (class "Default")
      (node (ref "U3") (pin "8") (pinfunction "PGOOD_8") (pintype "output"))
    )
    (net (code "72") (name "unconnected-(U4-NC-Pad7)") (class "Default")
      (node (ref "U4") (pin "7") (pinfunction "NC_7") (pintype "no_connect"))
    )
    (net (code "73") (name "unconnected-(U4-NC_2-Pad8)") (class "Default")
      (node (ref "U4") (pin "8") (pinfunction "NC_2_8") (pintype "no_connect"))
    )
    (net (code "74") (name "unconnected-(U5-NC-Pad7)") (class "Default")
      (node (ref "U5") (pin "7") (pinfunction "NC_7") (pintype "no_connect"))
    )
    (net (code "75") (name "unconnected-(U5-NC_2-Pad8)") (class "Default")
      (node (ref "U5") (pin "8") (pinfunction "NC_2_8") (pintype "no_connect"))
    )
    (net (code "76") (name "unconnected-(U9-VDPM-Pad9)") (class "Default")
      (node (ref "U9") (pin "9") (pinfunction "VDPM_9") (pintype "input"))
    )
    (net (code "77") (name "unconnected-(U9-~{CHG}-Pad8)") (class "Default")
      (node (ref "U9") (pin "8") (pinfunction "~{CHG}_8") (pintype "output"))
    )
  )
)
